# 14.net
KiCad netlist of a schematic drawn in EasyEDA Pro
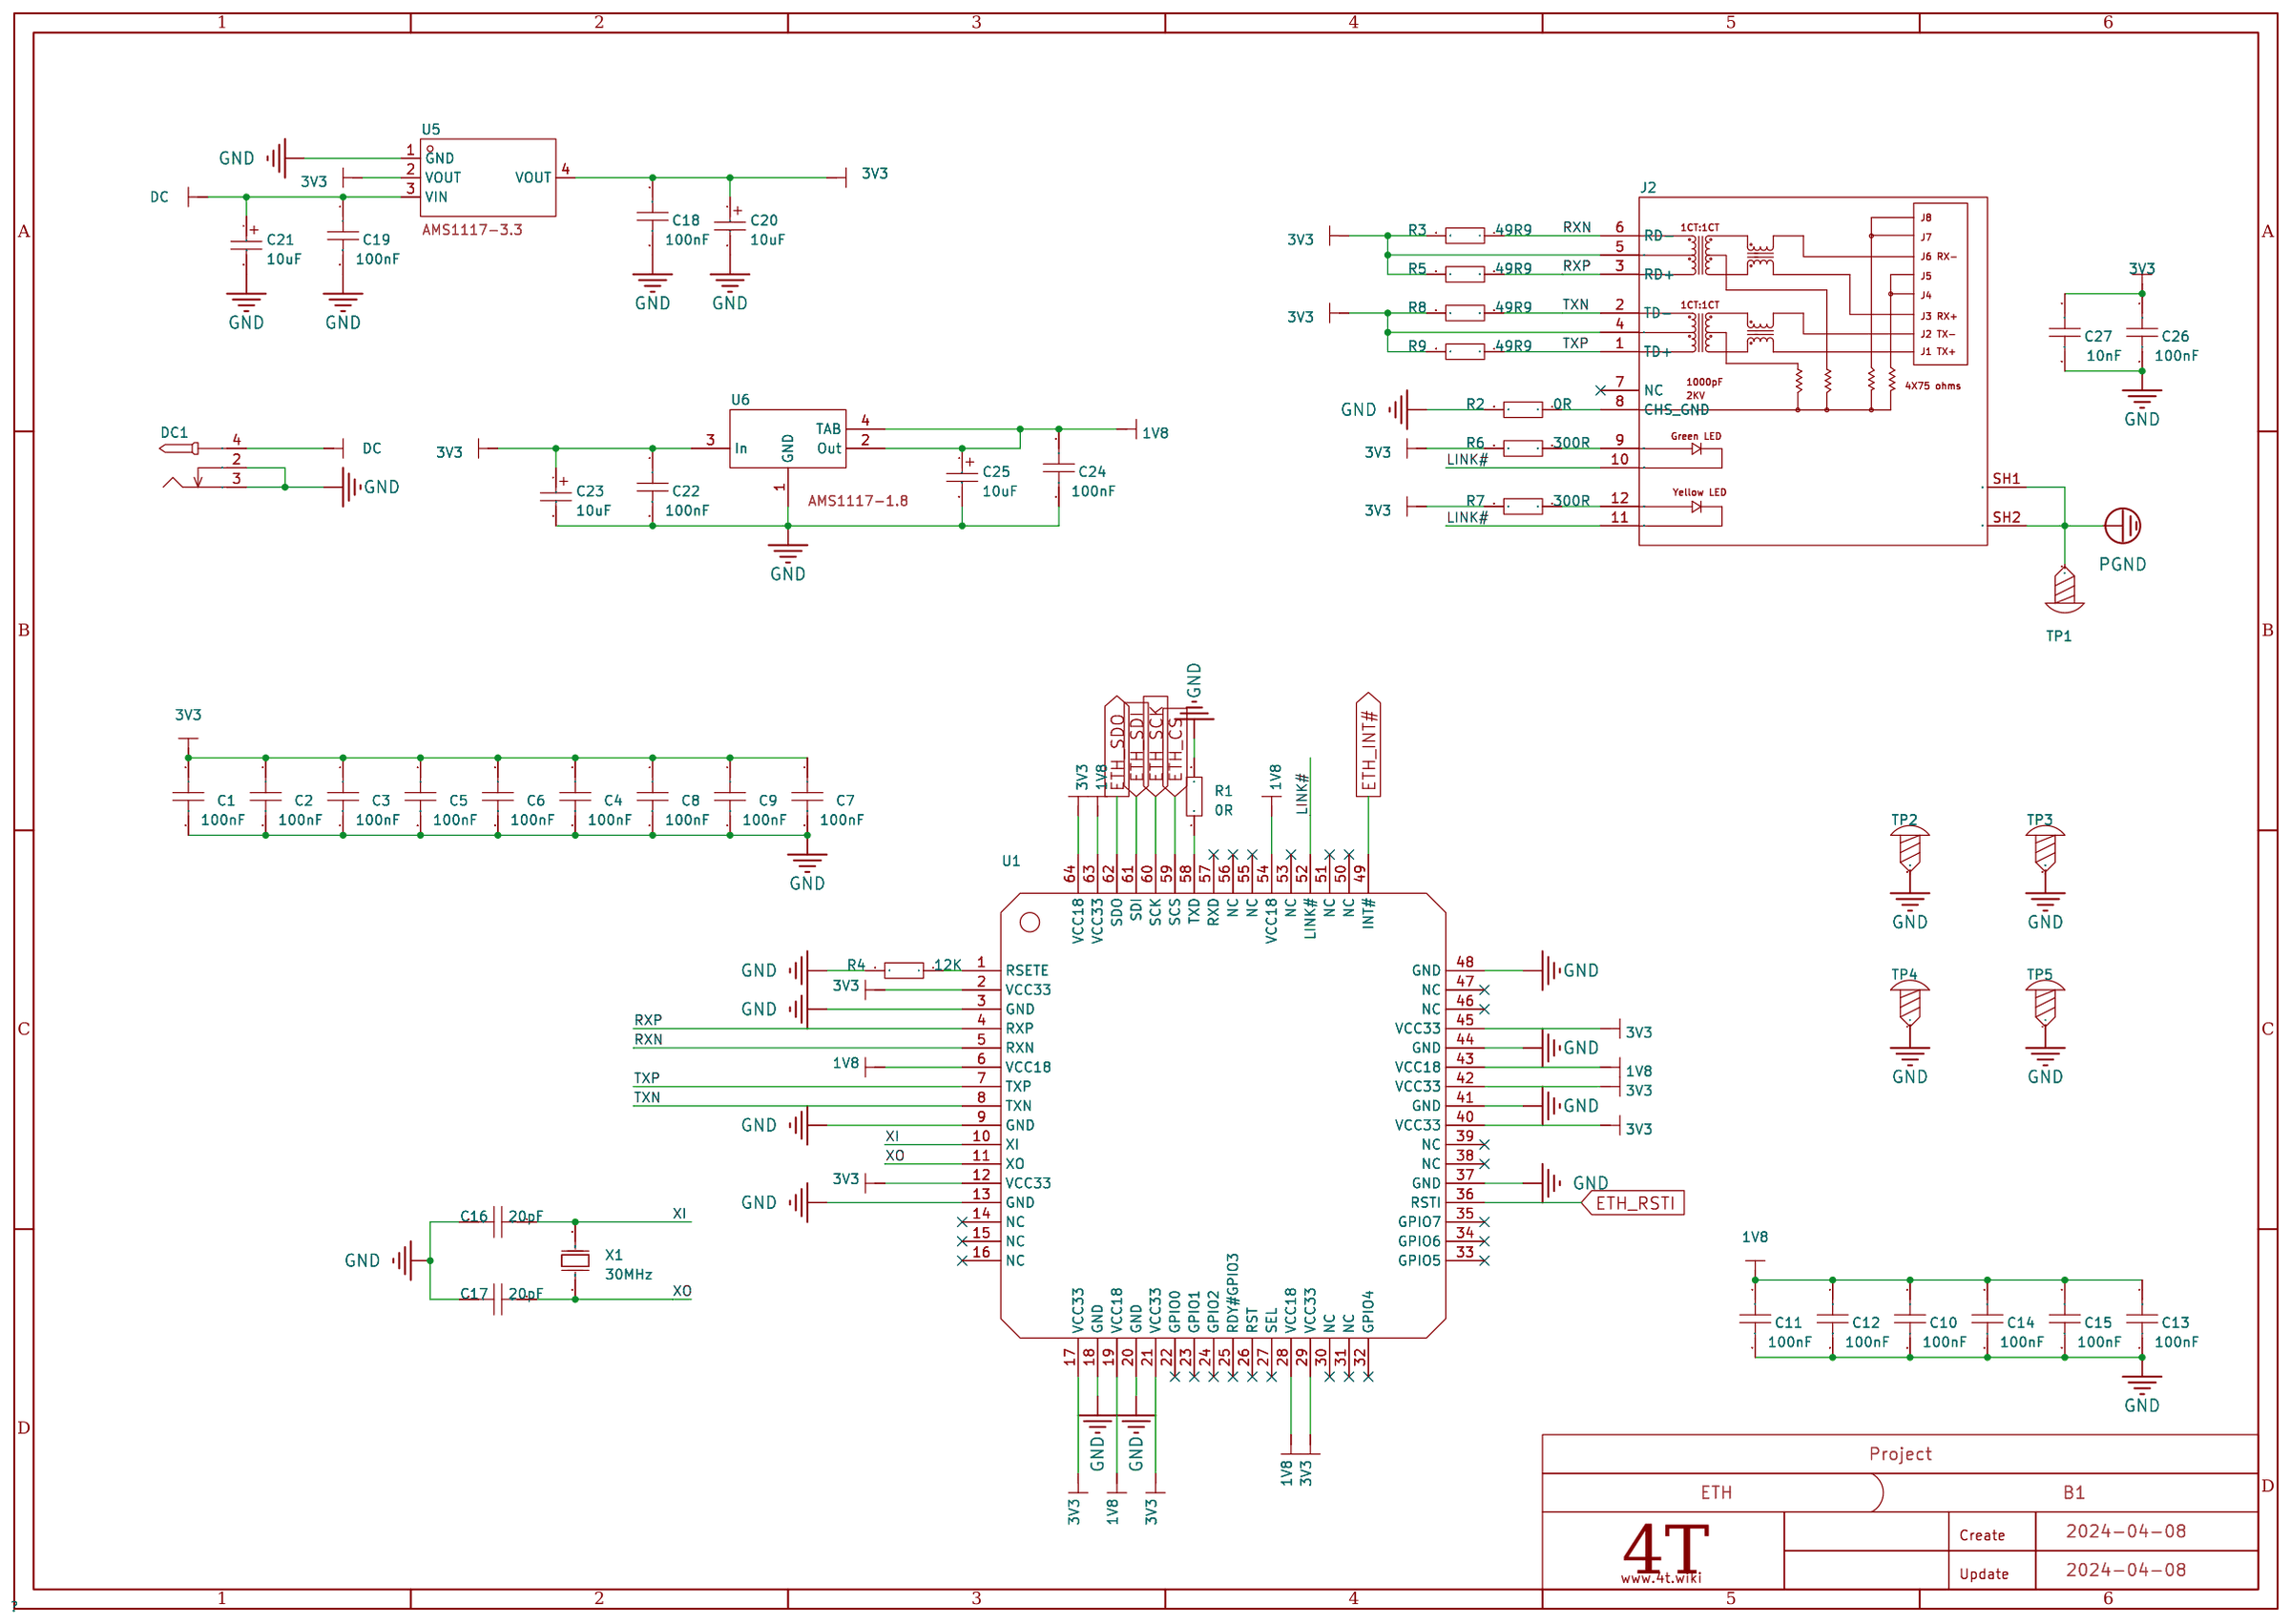
[diagram p0: ETH]
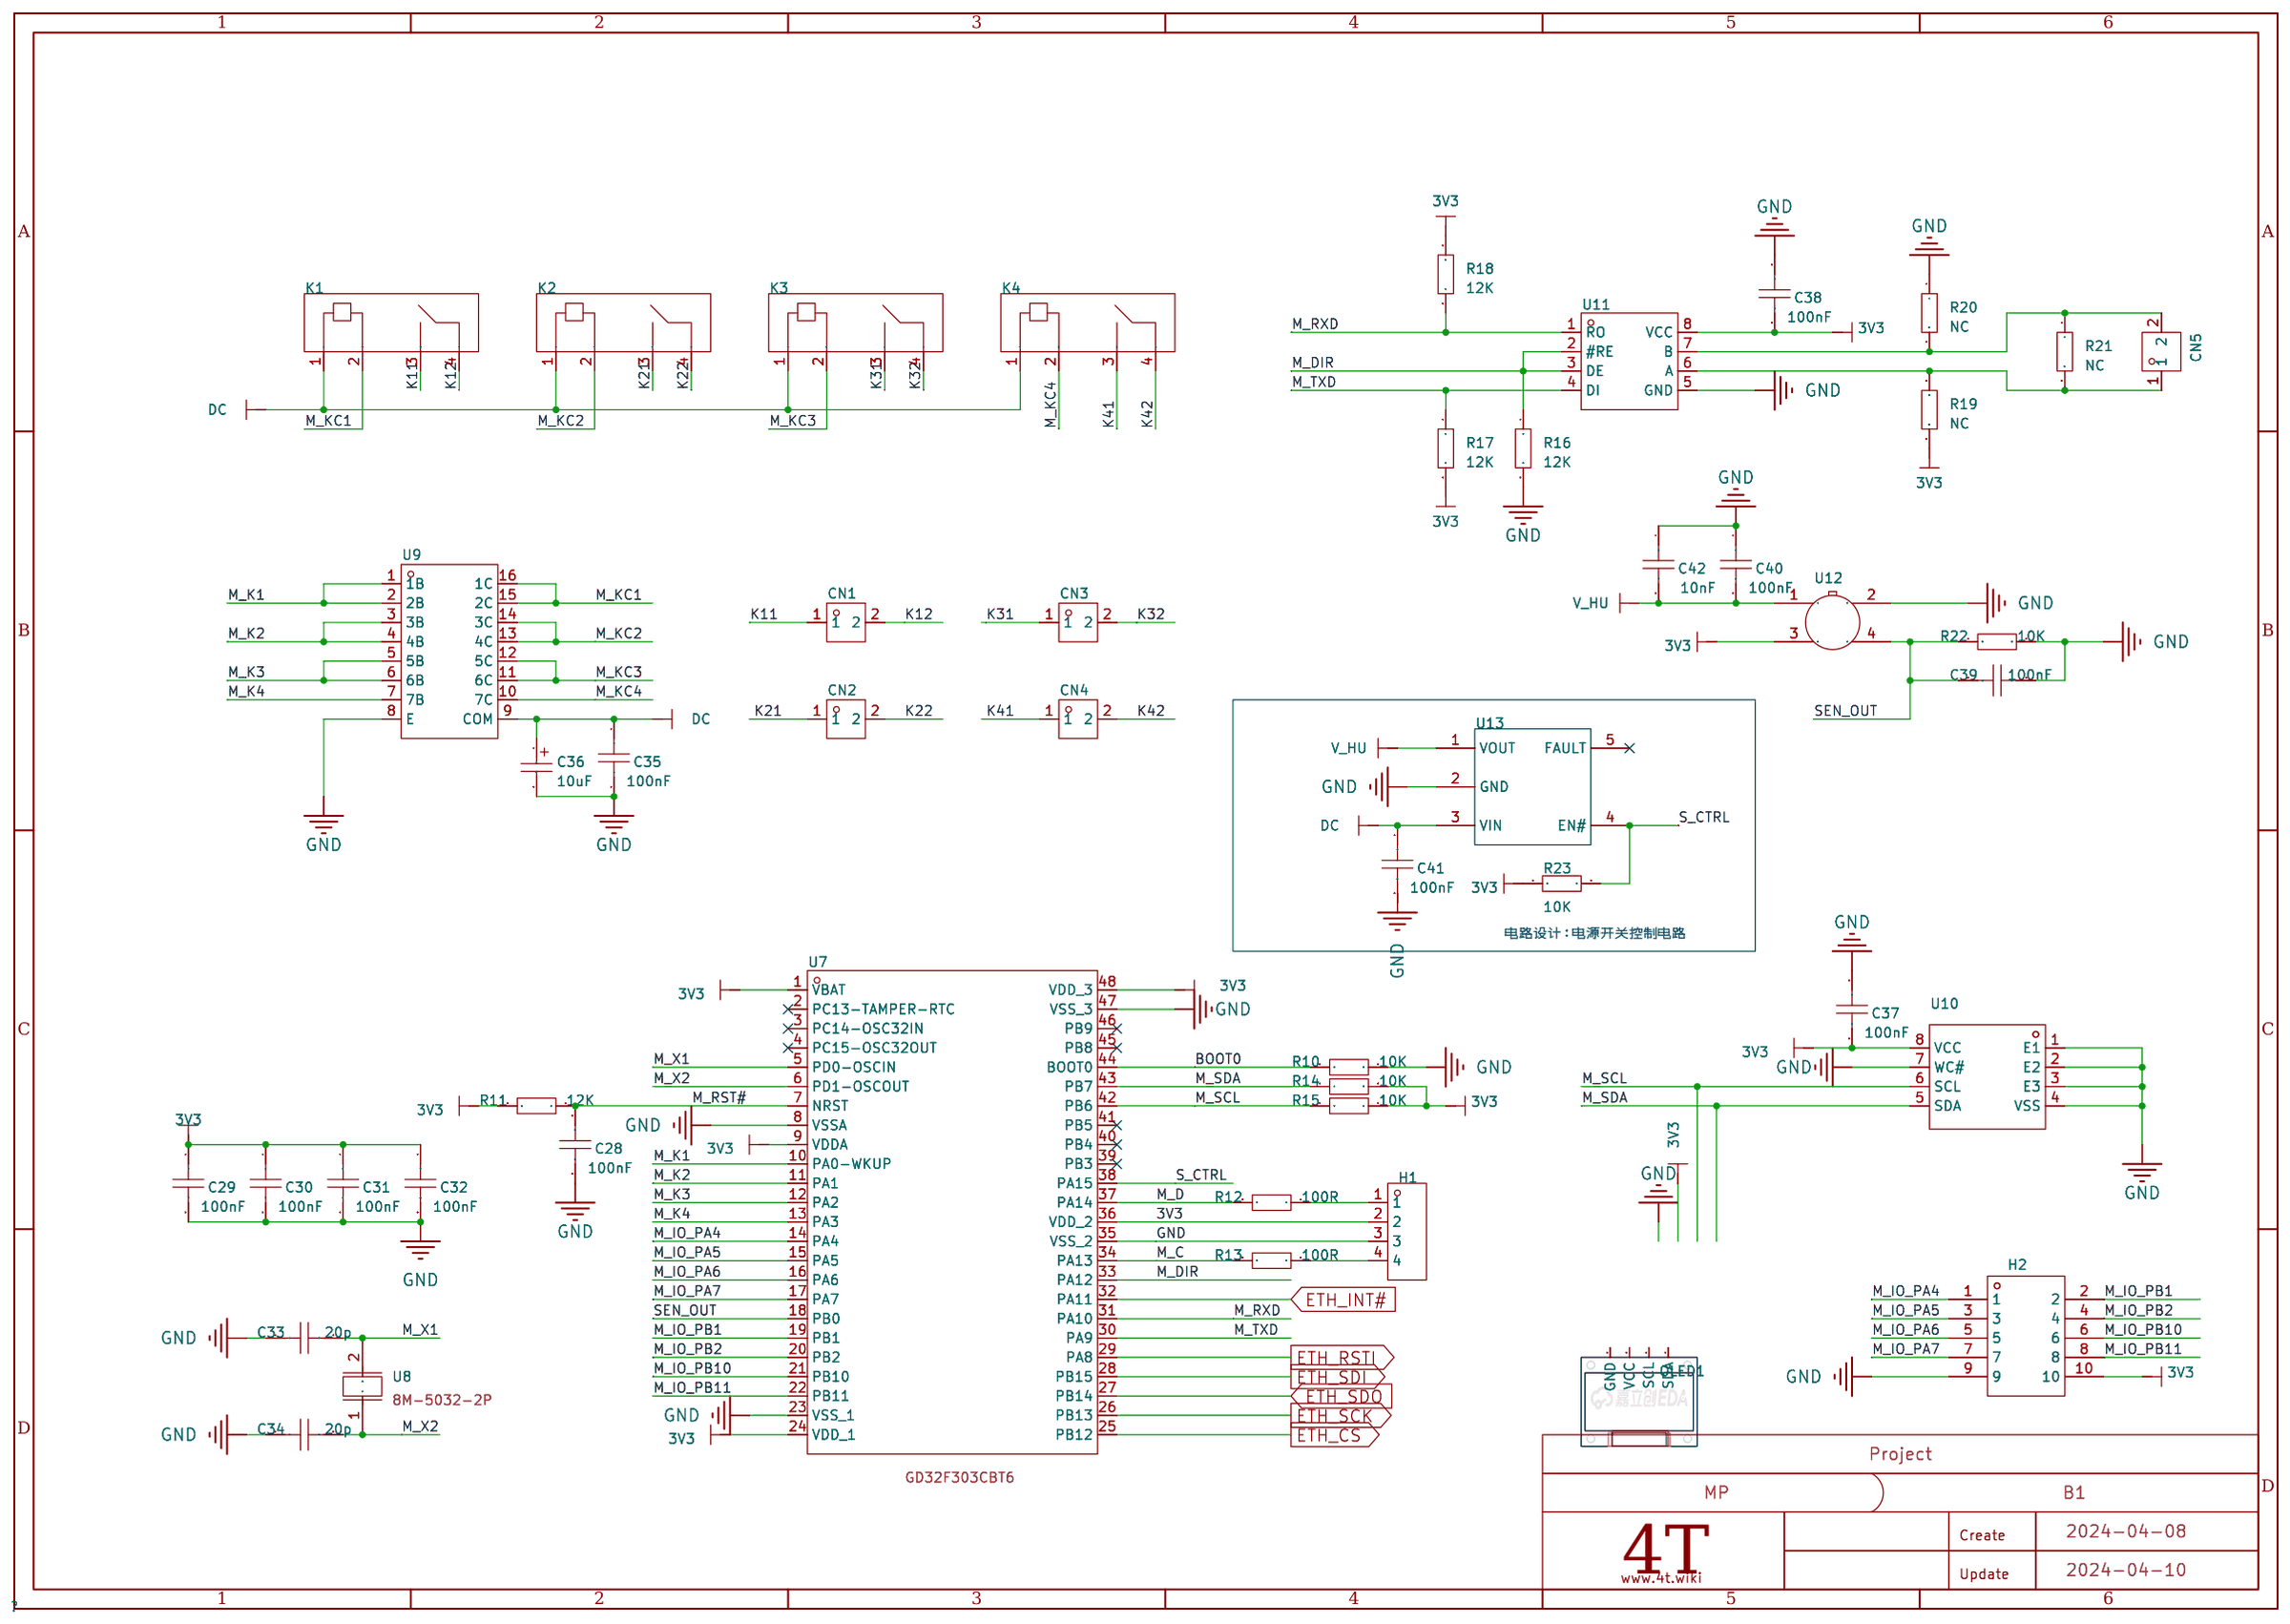
[diagram p1: MP]

(export (version "E")
  (design (tool "Eeschema 10.0.6"))
  (components
    (comp (ref "C1")
      (value "100nF")
      (footprint "easyedapro:C0805")
      (libsource (lib "easyedapro") (part "CapAcitance"))
    )
    (comp (ref "C2")
      (value "100nF")
      (footprint "easyedapro:C0805")
      (libsource (lib "easyedapro") (part "CapAcitance"))
    )
    (comp (ref "C3")
      (value "100nF")
      (footprint "easyedapro:C0805")
      (libsource (lib "easyedapro") (part "CapAcitance"))
    )
    (comp (ref "C4")
      (value "100nF")
      (footprint "easyedapro:C0805")
      (libsource (lib "easyedapro") (part "CapAcitance"))
    )
    (comp (ref "C5")
      (value "100nF")
      (footprint "easyedapro:C0805")
      (libsource (lib "easyedapro") (part "CapAcitance"))
    )
    (comp (ref "C6")
      (value "100nF")
      (footprint "easyedapro:C0805")
      (libsource (lib "easyedapro") (part "CapAcitance"))
    )
    (comp (ref "C7")
      (value "100nF")
      (footprint "easyedapro:C0805")
      (libsource (lib "easyedapro") (part "CapAcitance"))
    )
    (comp (ref "C8")
      (value "100nF")
      (footprint "easyedapro:C0805")
      (libsource (lib "easyedapro") (part "CapAcitance"))
    )
    (comp (ref "C9")
      (value "100nF")
      (footprint "easyedapro:C0805")
      (libsource (lib "easyedapro") (part "CapAcitance"))
    )
    (comp (ref "C10")
      (value "100nF")
      (footprint "easyedapro:C0805")
      (libsource (lib "easyedapro") (part "CapAcitance"))
    )
    (comp (ref "C11")
      (value "100nF")
      (footprint "easyedapro:C0805")
      (libsource (lib "easyedapro") (part "CapAcitance"))
    )
    (comp (ref "C12")
      (value "100nF")
      (footprint "easyedapro:C0805")
      (libsource (lib "easyedapro") (part "CapAcitance"))
    )
    (comp (ref "C13")
      (value "100nF")
      (footprint "easyedapro:C0805")
      (libsource (lib "easyedapro") (part "CapAcitance"))
    )
    (comp (ref "C14")
      (value "100nF")
      (footprint "easyedapro:C0805")
      (libsource (lib "easyedapro") (part "CapAcitance"))
    )
    (comp (ref "C15")
      (value "100nF")
      (footprint "easyedapro:C0805")
      (libsource (lib "easyedapro") (part "CapAcitance"))
    )
    (comp (ref "C16")
      (value "20pF")
      (footprint "easyedapro:C0805")
      (libsource (lib "easyedapro") (part "CapAcitance"))
    )
    (comp (ref "C17")
      (value "20pF")
      (footprint "easyedapro:C0805")
      (libsource (lib "easyedapro") (part "CapAcitance"))
    )
    (comp (ref "C18")
      (value "100nF")
      (footprint "easyedapro:C0805")
      (libsource (lib "easyedapro") (part "CapAcitance"))
    )
    (comp (ref "C19")
      (value "100nF")
      (footprint "easyedapro:C0805")
      (libsource (lib "easyedapro") (part "CapAcitance"))
    )
    (comp (ref "C20")
      (value "10uF")
      (footprint "easyedapro:C_Ele_SMD_3x5.4mm")
      (libsource (lib "easyedapro") (part "CAP"))
    )
    (comp (ref "C21")
      (value "10uF")
      (footprint "easyedapro:C_Ele_SMD_3x5.4mm")
      (libsource (lib "easyedapro") (part "CAP"))
    )
    (comp (ref "C22")
      (value "100nF")
      (footprint "easyedapro:C0805")
      (libsource (lib "easyedapro") (part "CapAcitance"))
    )
    (comp (ref "C23")
      (value "10uF")
      (footprint "easyedapro:C_Ele_SMD_3x5.4mm")
      (libsource (lib "easyedapro") (part "CAP"))
    )
    (comp (ref "C24")
      (value "100nF")
      (footprint "easyedapro:C0805")
      (libsource (lib "easyedapro") (part "CapAcitance"))
    )
    (comp (ref "C25")
      (value "10uF")
      (footprint "easyedapro:C_Ele_SMD_3x5.4mm")
      (libsource (lib "easyedapro") (part "CAP"))
    )
    (comp (ref "C26")
      (value "100nF")
      (footprint "easyedapro:C0805")
      (libsource (lib "easyedapro") (part "CapAcitance"))
    )
    (comp (ref "C27")
      (value "10nF")
      (footprint "easyedapro:C0805")
      (libsource (lib "easyedapro") (part "CapAcitance"))
    )
    (comp (ref "DC1")
      (value "~")
      (footprint "easyedapro:DC-2.0")
      (libsource (lib "easyedapro") (part "DC电源接口"))
    )
    (comp (ref "J2")
      (value "HY911105AE")
      (footprint "easyedapro:RJ45-TH_HR911105A")
      (description "连接器类型:RJ插座;USOC代码:RJ45;端口数量:1;等级:-;屏蔽:-;LED:-;")
      (fields (field (name "Manufacturer") "HANRUN(汉仁)"))
      (libsource (lib "easyedapro") (part "HY911105AE"))
    )
    (comp (ref "R1") (value "0R") (footprint "easyedapro:R0805") (libsource (lib "easyedapro") (part "电阻")))
    (comp (ref "R2") (value "0R") (footprint "easyedapro:R0805") (libsource (lib "easyedapro") (part "电阻")))
    (comp (ref "R3") (value "49R9") (footprint "easyedapro:R0805") (libsource (lib "easyedapro") (part "电阻")))
    (comp (ref "R4") (value "12K") (footprint "easyedapro:R0805") (libsource (lib "easyedapro") (part "电阻")))
    (comp (ref "R5") (value "49R9") (footprint "easyedapro:R0805") (libsource (lib "easyedapro") (part "电阻")))
    (comp (ref "R6") (value "300R") (footprint "easyedapro:R0805") (libsource (lib "easyedapro") (part "电阻")))
    (comp (ref "R7") (value "300R") (footprint "easyedapro:R0805") (libsource (lib "easyedapro") (part "电阻")))
    (comp (ref "R8") (value "49R9") (footprint "easyedapro:R0805") (libsource (lib "easyedapro") (part "电阻")))
    (comp (ref "R9") (value "49R9") (footprint "easyedapro:R0805") (libsource (lib "easyedapro") (part "电阻")))
    (comp (ref "TP1") (value "~") (footprint "easyedapro:M2螺丝") (libsource (lib "easyedapro") (part "螺丝孔")))
    (comp (ref "TP2") (value "~") (footprint "easyedapro:M2螺丝") (libsource (lib "easyedapro") (part "螺丝孔")))
    (comp (ref "TP3") (value "~") (footprint "easyedapro:M2螺丝") (libsource (lib "easyedapro") (part "螺丝孔")))
    (comp (ref "TP4") (value "~") (footprint "easyedapro:M2螺丝") (libsource (lib "easyedapro") (part "螺丝孔")))
    (comp (ref "TP5") (value "~") (footprint "easyedapro:M2螺丝") (libsource (lib "easyedapro") (part "螺丝孔")))
    (comp (ref "U1")
      (value "CH395Q")
      (footprint "easyedapro:LQFP-64_L10.0-W10.0-P0.50-LS12.0-BL")
      (description "应用功能:以太网控制器;通道数:-;接口类型:Parallel, SPI, UART;电源电压:1.65V~3.6V;电源电流:90mA;")
      (fields (field (name "Manufacturer") "WCH(南京沁恒)"))
      (libsource (lib "easyedapro") (part "CH395Q"))
    )
    (comp (ref "U5")
      (value "AMS1117-3.3")
      (footprint "easyedapro:SOT-223-3_L6.5-W3.4-P2.30-LS7.0-BR")
      (fields (field (name "Manufacturer Part") "AMS1117-3.3") (field (name "Manufacturer") "AMS"))
      (libsource (lib "easyedapro") (part "AMS1117-3.3"))
    )
    (comp (ref "U6")
      (value "AMS1117-1.8")
      (footprint "easyedapro:SOT-223-4_L6.5-W3.5-P2.30-LS7.0-BR")
      (description "输出类型:固定;输出极性:正;输出通道数:1;最大输入电压:15V;输出电压:1.8V~1.8V;压差:1.3V@(1A);输出电流:1A;电源纹波抑制比(PSRR):75dB@(120Hz);")
      (fields (field (name "Manufacturer Part") "AMS1117-1.8") (field (name "Manufacturer") "AMS"))
      (libsource (lib "easyedapro") (part "AMS1117-1.8"))
    )
    (comp (ref "X1")
      (value "30MHz")
      (footprint "easyedapro:OSC-SMD_L5.0-W3.2")
      (description "晶振类型:贴片无源晶振;频率:30MHz;频率公差:±10ppm;频率稳定度:±50ppm;负载电容:20pF;工作温度:-40℃~+85℃;")
      (fields (field (name "Manufacturer Part") "X503230MSB2GI") (field (name "Manufacturer") "YXC(扬兴晶振)"))
      (libsource (lib "easyedapro") (part "X503230MSB2GI"))
    )
    (comp (ref "C28")
      (value "100nF")
      (footprint "easyedapro:C0805")
      (libsource (lib "easyedapro") (part "CapAcitance"))
    )
    (comp (ref "C29")
      (value "100nF")
      (footprint "easyedapro:C0805")
      (libsource (lib "easyedapro") (part "CapAcitance"))
    )
    (comp (ref "C30")
      (value "100nF")
      (footprint "easyedapro:C0805")
      (libsource (lib "easyedapro") (part "CapAcitance"))
    )
    (comp (ref "C31")
      (value "100nF")
      (footprint "easyedapro:C0805")
      (libsource (lib "easyedapro") (part "CapAcitance"))
    )
    (comp (ref "C32")
      (value "100nF")
      (footprint "easyedapro:C0805")
      (libsource (lib "easyedapro") (part "CapAcitance"))
    )
    (comp (ref "C33")
      (value "20p")
      (footprint "easyedapro:C0805")
      (libsource (lib "easyedapro") (part "CapAcitance"))
    )
    (comp (ref "C34")
      (value "20p")
      (footprint "easyedapro:C0805")
      (libsource (lib "easyedapro") (part "CapAcitance"))
    )
    (comp (ref "C35")
      (value "100nF")
      (footprint "easyedapro:C0805")
      (libsource (lib "easyedapro") (part "CapAcitance"))
    )
    (comp (ref "C36")
      (value "10uF")
      (footprint "easyedapro:C_Ele_SMD_3x5.4mm")
      (libsource (lib "easyedapro") (part "CAP"))
    )
    (comp (ref "C37")
      (value "100nF")
      (footprint "easyedapro:C0805")
      (libsource (lib "easyedapro") (part "CapAcitance"))
    )
    (comp (ref "C38")
      (value "100nF")
      (footprint "easyedapro:C0805")
      (libsource (lib "easyedapro") (part "CapAcitance"))
    )
    (comp (ref "C39")
      (value "100nF")
      (footprint "easyedapro:C0805")
      (libsource (lib "easyedapro") (part "CapAcitance"))
    )
    (comp (ref "C40")
      (value "100nF")
      (footprint "easyedapro:C0805")
      (libsource (lib "easyedapro") (part "CapAcitance"))
    )
    (comp (ref "C41")
      (value "100nF")
      (footprint "easyedapro:C0805")
      (libsource (lib "easyedapro") (part "CapAcitance"))
    )
    (comp (ref "C42")
      (value "10nF")
      (footprint "easyedapro:C0805")
      (libsource (lib "easyedapro") (part "CapAcitance"))
    )
    (comp (ref "CN1")
      (value "KF128L-5.08-2P 蓝色")
      (footprint "easyedapro:TH_KF128L-5.08-2P")
      (libsource (lib "easyedapro") (part "KF128L-5.08-2P 蓝色"))
    )
    (comp (ref "CN2")
      (value "KF128L-5.08-2P 蓝色")
      (footprint "easyedapro:TH_KF128L-5.08-2P")
      (libsource (lib "easyedapro") (part "KF128L-5.08-2P 蓝色"))
    )
    (comp (ref "CN3")
      (value "KF128L-5.08-2P 蓝色")
      (footprint "easyedapro:TH_KF128L-5.08-2P")
      (libsource (lib "easyedapro") (part "KF128L-5.08-2P 蓝色"))
    )
    (comp (ref "CN4")
      (value "KF128L-5.08-2P 蓝色")
      (footprint "easyedapro:TH_KF128L-5.08-2P")
      (libsource (lib "easyedapro") (part "KF128L-5.08-2P 蓝色"))
    )
    (comp (ref "CN5")
      (value "KF128L-5.08-2P 蓝色")
      (footprint "easyedapro:TH_KF128L-5.08-2P")
      (libsource (lib "easyedapro") (part "KF128L-5.08-2P 蓝色"))
    )
    (comp (ref "H1")
      (value "~")
      (footprint "easyedapro:HDR-TH_4P-P2.54-V-F")
      (libsource (lib "easyedapro") (part "2.54-1*4P母"))
    )
    (comp (ref "H2")
      (value "~")
      (footprint "easyedapro:HDR-TH_10P-P2.54-V-M-R2-C5-S2.54")
      (libsource (lib "easyedapro") (part "HDR-M-2.54_2x5"))
    )
    (comp (ref "K1")
      (value "HF49FD/012-1H12")
      (footprint "easyedapro:RELAY-TH_HF49FD-XXX-1H12-XXX")
      (description "线圈电压:12V;线圈类型:非极化-单线圈;触点形式:一组常开:1A(单刀单掷-常开);最大切换电流:5A;触点材料:AgNi;")
      (fields (field (name "Manufacturer") "HF(宏发)"))
      (libsource (lib "easyedapro") (part "HF49FD/012-1H12"))
    )
    (comp (ref "K2")
      (value "HF49FD/012-1H12")
      (footprint "easyedapro:RELAY-TH_HF49FD-XXX-1H12-XXX")
      (description "线圈电压:12V;线圈类型:非极化-单线圈;触点形式:一组常开:1A(单刀单掷-常开);最大切换电流:5A;触点材料:AgNi;")
      (fields (field (name "Manufacturer") "HF(宏发)"))
      (libsource (lib "easyedapro") (part "HF49FD/012-1H12"))
    )
    (comp (ref "K3")
      (value "HF49FD/012-1H12")
      (footprint "easyedapro:RELAY-TH_HF49FD-XXX-1H12-XXX")
      (description "线圈电压:12V;线圈类型:非极化-单线圈;触点形式:一组常开:1A(单刀单掷-常开);最大切换电流:5A;触点材料:AgNi;")
      (fields (field (name "Manufacturer") "HF(宏发)"))
      (libsource (lib "easyedapro") (part "HF49FD/012-1H12"))
    )
    (comp (ref "K4")
      (value "HF49FD/012-1H12")
      (footprint "easyedapro:RELAY-TH_HF49FD-XXX-1H12-XXX")
      (description "线圈电压:12V;线圈类型:非极化-单线圈;触点形式:一组常开:1A(单刀单掷-常开);最大切换电流:5A;触点材料:AgNi;")
      (fields (field (name "Manufacturer") "HF(宏发)"))
      (libsource (lib "easyedapro") (part "HF49FD/012-1H12"))
    )
    (comp (ref "OLED1")
      (value "~")
      (footprint "easyedapro:0.96OLED_4P")
      (libsource (lib "easyedapro") (part "0.96OLED模块_4P"))
    )
    (comp (ref "R10") (value "10K") (footprint "easyedapro:R0805") (libsource (lib "easyedapro") (part "电阻")))
    (comp (ref "R11") (value "12K") (footprint "easyedapro:R0805") (libsource (lib "easyedapro") (part "电阻")))
    (comp (ref "R12")
      (value "100R")
      (footprint "easyedapro:R0805")
      (libsource (lib "easyedapro") (part "电阻"))
    )
    (comp (ref "R13")
      (value "100R")
      (footprint "easyedapro:R0805")
      (libsource (lib "easyedapro") (part "电阻"))
    )
    (comp (ref "R14") (value "10K") (footprint "easyedapro:R0805") (libsource (lib "easyedapro") (part "电阻")))
    (comp (ref "R15") (value "10K") (footprint "easyedapro:R0805") (libsource (lib "easyedapro") (part "电阻")))
    (comp (ref "R16") (value "12K") (footprint "easyedapro:R0805") (libsource (lib "easyedapro") (part "电阻")))
    (comp (ref "R17") (value "12K") (footprint "easyedapro:R0805") (libsource (lib "easyedapro") (part "电阻")))
    (comp (ref "R18") (value "12K") (footprint "easyedapro:R0805") (libsource (lib "easyedapro") (part "电阻")))
    (comp (ref "R19") (value "NC") (footprint "easyedapro:R0805") (libsource (lib "easyedapro") (part "电阻")))
    (comp (ref "R20") (value "NC") (footprint "easyedapro:R0805") (libsource (lib "easyedapro") (part "电阻")))
    (comp (ref "R21") (value "NC") (footprint "easyedapro:R0805") (libsource (lib "easyedapro") (part "电阻")))
    (comp (ref "R22") (value "10K") (footprint "easyedapro:R0805") (libsource (lib "easyedapro") (part "电阻")))
    (comp (ref "R23") (value "10K") (footprint "easyedapro:R0805") (libsource (lib "easyedapro") (part "电阻")))
    (comp (ref "U7")
      (value "GD32F303CBT6")
      (footprint "easyedapro:LQFP-48_L7.0-W7.0-P0.50-LS9.0-BL")
      (fields
        (field (name "Manufacturer Part") "GD32F303CBT6")
        (field (name "Manufacturer") "GigaDevice(兆易创新)")
      )
      (libsource (lib "easyedapro") (part "GD32F303CBT6"))
    )
    (comp (ref "U8")
      (value "8M-5032-2P")
      (footprint "easyedapro:CRYSTAL-SMD_L5.0-W3.2")
      (fields (field (name "Manufacturer Part") "8M-5032-2P"))
      (libsource (lib "easyedapro") (part "8M-5032-2P"))
    )
    (comp (ref "U9")
      (value "ULN2003")
      (footprint "easyedapro:SOIC-16_L9.9-W3.9-P1.27-LS6.0-BL")
      (fields (field (name "Manufacturer") "IDCHIP(英锐芯)"))
      (libsource (lib "easyedapro") (part "ULN2003_C688859"))
    )
    (comp (ref "U10")
      (value "M24C02-WMN6TP")
      (footprint "easyedapro:SOIC-8_L4.9-W3.9-P1.27-LS6.0-BL")
      (description "2-Kbit(256 x 8bit)，I2C接口，工作电压：2.5V to 5.5V")
      (fields (field (name "Manufacturer") "ST(意法半导体)"))
      (libsource (lib "easyedapro") (part "M24C02-WMN6TP"))
    )
    (comp (ref "U11")
      (value "MAX3485ESA")
      (footprint "easyedapro:SOP-8_L5.0-W4.0-P1.27-LS6.0-BL")
      (fields (field (name "Manufacturer") "UMW(广东友台半导体)"))
      (libsource (lib "easyedapro") (part "MAX3485ESA"))
    )
    (comp (ref "U12")
      (value "MP-2")
      (footprint "easyedapro:SENSOR-TH_MP-5")
      (fields (field (name "Manufacturer") "Winsen(炜盛)"))
      (libsource (lib "easyedapro") (part "MP-2"))
    )
    (comp (ref "U13")
      (value "~")
      (footprint "easyedapro:SOT_PDS")
      (libsource (lib "easyedapro") (part "PDS"))
    )
  )
  (nets
    (net (code "1") (name "1V8") (class "Default")
      (node (ref "C10") (pin "1") (pinfunction "1_1") (pintype "input"))
      (node (ref "C11") (pin "1") (pinfunction "1_1") (pintype "input"))
      (node (ref "C12") (pin "1") (pinfunction "1_1") (pintype "input"))
      (node (ref "C13") (pin "1") (pinfunction "1_1") (pintype "input"))
      (node (ref "C14") (pin "1") (pinfunction "1_1") (pintype "input"))
      (node (ref "C15") (pin "1") (pinfunction "1_1") (pintype "input"))
      (node (ref "C24") (pin "1") (pinfunction "1_1") (pintype "input"))
      (node (ref "C25") (pin "1") (pinfunction "1_1") (pintype "input"))
      (node (ref "U1") (pin "19") (pinfunction "VCC18_19") (pintype "input"))
      (node (ref "U1") (pin "28") (pinfunction "VCC18_28") (pintype "input"))
      (node (ref "U1") (pin "43") (pinfunction "VCC18_43") (pintype "input"))
      (node (ref "U1") (pin "54") (pinfunction "VCC18_54") (pintype "input"))
      (node (ref "U1") (pin "6") (pinfunction "VCC18_6") (pintype "input"))
      (node (ref "U1") (pin "63") (pinfunction "VCC33_63") (pintype "input"))
      (node (ref "U6") (pin "2") (pinfunction "Out_2") (pintype "input"))
      (node (ref "U6") (pin "4") (pinfunction "TAB_4") (pintype "input"))
    )
    (net (code "2") (name "3V3") (class "Default")
      (node (ref "C1") (pin "1") (pinfunction "1_1") (pintype "input"))
      (node (ref "C18") (pin "1") (pinfunction "1_1") (pintype "input"))
      (node (ref "C2") (pin "1") (pinfunction "1_1") (pintype "input"))
      (node (ref "C20") (pin "1") (pinfunction "1_1") (pintype "input"))
      (node (ref "C22") (pin "1") (pinfunction "1_1") (pintype "input"))
      (node (ref "C23") (pin "1") (pinfunction "1_1") (pintype "input"))
      (node (ref "C26") (pin "1") (pinfunction "1_1") (pintype "input"))
      (node (ref "C27") (pin "1") (pinfunction "1_1") (pintype "input"))
      (node (ref "C29") (pin "1") (pinfunction "1_1") (pintype "input"))
      (node (ref "C3") (pin "1") (pinfunction "1_1") (pintype "input"))
      (node (ref "C30") (pin "1") (pinfunction "1_1") (pintype "input"))
      (node (ref "C31") (pin "1") (pinfunction "1_1") (pintype "input"))
      (node (ref "C32") (pin "1") (pinfunction "1_1") (pintype "input"))
      (node (ref "C37") (pin "2") (pinfunction "2_2") (pintype "input"))
      (node (ref "C38") (pin "2") (pinfunction "2_2") (pintype "input"))
      (node (ref "C4") (pin "1") (pinfunction "1_1") (pintype "input"))
      (node (ref "C5") (pin "1") (pinfunction "1_1") (pintype "input"))
      (node (ref "C6") (pin "1") (pinfunction "1_1") (pintype "input"))
      (node (ref "C7") (pin "1") (pinfunction "1_1") (pintype "input"))
      (node (ref "C8") (pin "1") (pinfunction "1_1") (pintype "input"))
      (node (ref "C9") (pin "1") (pinfunction "1_1") (pintype "input"))
      (node (ref "H1") (pin "2") (pinfunction "2_2") (pintype "input"))
      (node (ref "H2") (pin "10") (pinfunction "10_10") (pintype "input"))
      (node (ref "J2") (pin "4") (pinfunction "4_4") (pintype "input"))
      (node (ref "J2") (pin "5") (pinfunction "5_5") (pintype "input"))
      (node (ref "R11") (pin "2") (pinfunction "2_2") (pintype "input"))
      (node (ref "R14") (pin "2") (pinfunction "2_2") (pintype "input"))
      (node (ref "R15") (pin "1") (pinfunction "1_1") (pintype "input"))
      (node (ref "R17") (pin "2") (pinfunction "2_2") (pintype "input"))
      (node (ref "R18") (pin "1") (pinfunction "1_1") (pintype "input"))
      (node (ref "R19") (pin "2") (pinfunction "2_2") (pintype "input"))
      (node (ref "R23") (pin "1") (pinfunction "1_1") (pintype "input"))
      (node (ref "R3") (pin "2") (pinfunction "2_2") (pintype "input"))
      (node (ref "R5") (pin "2") (pinfunction "2_2") (pintype "input"))
      (node (ref "R6") (pin "2") (pinfunction "2_2") (pintype "input"))
      (node (ref "R7") (pin "2") (pinfunction "2_2") (pintype "input"))
      (node (ref "R8") (pin "2") (pinfunction "2_2") (pintype "input"))
      (node (ref "R9") (pin "2") (pinfunction "2_2") (pintype "input"))
      (node (ref "U1") (pin "12") (pinfunction "VCC33_12") (pintype "input"))
      (node (ref "U1") (pin "17") (pinfunction "VCC33_17") (pintype "input"))
      (node (ref "U1") (pin "2") (pinfunction "VCC33_2") (pintype "input"))
      (node (ref "U1") (pin "21") (pinfunction "VCC33_21") (pintype "input"))
      (node (ref "U1") (pin "29") (pinfunction "VCC33_29") (pintype "input"))
      (node (ref "U1") (pin "40") (pinfunction "VCC33_40") (pintype "input"))
      (node (ref "U1") (pin "42") (pinfunction "VCC33_42") (pintype "input"))
      (node (ref "U1") (pin "45") (pinfunction "VCC33_45") (pintype "input"))
      (node (ref "U1") (pin "64") (pinfunction "VCC18_64") (pintype "input"))
      (node (ref "U10") (pin "8") (pinfunction "VCC_8") (pintype "input"))
      (node (ref "U11") (pin "8") (pinfunction "VCC_8") (pintype "input"))
      (node (ref "U12") (pin "3") (pinfunction "3_3") (pintype "input"))
      (node (ref "U5") (pin "2") (pinfunction "VOUT_2") (pintype "input"))
      (node (ref "U5") (pin "4") (pinfunction "VOUT_4") (pintype "input"))
      (node (ref "U6") (pin "3") (pinfunction "In_3") (pintype "input"))
      (node (ref "U7") (pin "1") (pinfunction "VBAT_1") (pintype "input"))
      (node (ref "U7") (pin "24") (pinfunction "VDD_1_24") (pintype "input"))
      (node (ref "U7") (pin "36") (pinfunction "VDD_2_36") (pintype "input"))
      (node (ref "U7") (pin "48") (pinfunction "VDD_3_48") (pintype "input"))
      (node (ref "U7") (pin "9") (pinfunction "VDDA_9") (pintype "input"))
    )
    (net (code "3") (name "BOOT0") (class "Default")
      (node (ref "R10") (pin "2") (pinfunction "2_2") (pintype "input"))
      (node (ref "U7") (pin "44") (pinfunction "BOOT0_44") (pintype "input"))
    )
    (net (code "4") (name "DC") (class "Default")
      (node (ref "C19") (pin "1") (pinfunction "1_1") (pintype "input"))
      (node (ref "C21") (pin "1") (pinfunction "1_1") (pintype "input"))
      (node (ref "C35") (pin "1") (pinfunction "1_1") (pintype "input"))
      (node (ref "C36") (pin "1") (pinfunction "1_1") (pintype "input"))
      (node (ref "C41") (pin "1") (pinfunction "1_1") (pintype "input"))
      (node (ref "DC1") (pin "4") (pinfunction "4_4") (pintype "input"))
      (node (ref "K1") (pin "1") (pinfunction "1_1") (pintype "input"))
      (node (ref "K2") (pin "1") (pinfunction "1_1") (pintype "input"))
      (node (ref "K3") (pin "1") (pinfunction "1_1") (pintype "input"))
      (node (ref "K4") (pin "1") (pinfunction "1_1") (pintype "input"))
      (node (ref "U13") (pin "3") (pinfunction "VIN_3") (pintype "input"))
      (node (ref "U5") (pin "3") (pinfunction "VIN_3") (pintype "input"))
      (node (ref "U9") (pin "9") (pinfunction "COM_9") (pintype "input"))
    )
    (net (code "5") (name "ETH_CS") (class "Default")
      (node (ref "U1") (pin "59") (pinfunction "SCS_59") (pintype "input"))
      (node (ref "U7") (pin "25") (pinfunction "PB12_25") (pintype "input"))
    )
    (net (code "6") (name "ETH_INT#") (class "Default")
      (node (ref "U1") (pin "49") (pinfunction "INT#_49") (pintype "input"))
      (node (ref "U7") (pin "32") (pinfunction "PA11_32") (pintype "input"))
    )
    (net (code "7") (name "ETH_RSTI") (class "Default")
      (node (ref "U1") (pin "36") (pinfunction "RSTI_36") (pintype "input"))
      (node (ref "U7") (pin "29") (pinfunction "PA8_29") (pintype "input"))
    )
    (net (code "8") (name "ETH_SCK") (class "Default")
      (node (ref "U1") (pin "60") (pinfunction "SCK_60") (pintype "input"))
      (node (ref "U7") (pin "26") (pinfunction "PB13_26") (pintype "input"))
    )
    (net (code "9") (name "ETH_SDI") (class "Default")
      (node (ref "U1") (pin "61") (pinfunction "SDI_61") (pintype "input"))
      (node (ref "U7") (pin "28") (pinfunction "PB15_28") (pintype "input"))
    )
    (net (code "10") (name "ETH_SDO") (class "Default")
      (node (ref "U1") (pin "62") (pinfunction "SDO_62") (pintype "input"))
      (node (ref "U7") (pin "27") (pinfunction "PB14_27") (pintype "input"))
    )
    (net (code "11") (name "GND") (class "Default")
      (node (ref "C1") (pin "2") (pinfunction "2_2") (pintype "input"))
      (node (ref "C10") (pin "2") (pinfunction "2_2") (pintype "input"))
      (node (ref "C11") (pin "2") (pinfunction "2_2") (pintype "input"))
      (node (ref "C12") (pin "2") (pinfunction "2_2") (pintype "input"))
      (node (ref "C13") (pin "2") (pinfunction "2_2") (pintype "input"))
      (node (ref "C14") (pin "2") (pinfunction "2_2") (pintype "input"))
      (node (ref "C15") (pin "2") (pinfunction "2_2") (pintype "input"))
      (node (ref "C16") (pin "1") (pinfunction "1_1") (pintype "input"))
      (node (ref "C17") (pin "1") (pinfunction "1_1") (pintype "input"))
      (node (ref "C18") (pin "2") (pinfunction "2_2") (pintype "input"))
      (node (ref "C19") (pin "2") (pinfunction "2_2") (pintype "input"))
      (node (ref "C2") (pin "2") (pinfunction "2_2") (pintype "input"))
      (node (ref "C20") (pin "2") (pinfunction "2_2") (pintype "input"))
      (node (ref "C21") (pin "2") (pinfunction "2_2") (pintype "input"))
      (node (ref "C22") (pin "2") (pinfunction "2_2") (pintype "input"))
      (node (ref "C23") (pin "2") (pinfunction "2_2") (pintype "input"))
      (node (ref "C24") (pin "2") (pinfunction "2_2") (pintype "input"))
      (node (ref "C25") (pin "2") (pinfunction "2_2") (pintype "input"))
      (node (ref "C26") (pin "2") (pinfunction "2_2") (pintype "input"))
      (node (ref "C27") (pin "2") (pinfunction "2_2") (pintype "input"))
      (node (ref "C28") (pin "2") (pinfunction "2_2") (pintype "input"))
      (node (ref "C29") (pin "2") (pinfunction "2_2") (pintype "input"))
      (node (ref "C3") (pin "2") (pinfunction "2_2") (pintype "input"))
      (node (ref "C30") (pin "2") (pinfunction "2_2") (pintype "input"))
      (node (ref "C31") (pin "2") (pinfunction "2_2") (pintype "input"))
      (node (ref "C32") (pin "2") (pinfunction "2_2") (pintype "input"))
      (node (ref "C33") (pin "1") (pinfunction "1_1") (pintype "input"))
      (node (ref "C34") (pin "1") (pinfunction "1_1") (pintype "input"))
      (node (ref "C35") (pin "2") (pinfunction "2_2") (pintype "input"))
      (node (ref "C36") (pin "2") (pinfunction "2_2") (pintype "input"))
      (node (ref "C37") (pin "1") (pinfunction "1_1") (pintype "input"))
      (node (ref "C38") (pin "1") (pinfunction "1_1") (pintype "input"))
      (node (ref "C39") (pin "2") (pinfunction "2_2") (pintype "input"))
      (node (ref "C4") (pin "2") (pinfunction "2_2") (pintype "input"))
      (node (ref "C40") (pin "1") (pinfunction "1_1") (pintype "input"))
      (node (ref "C41") (pin "2") (pinfunction "2_2") (pintype "input"))
      (node (ref "C42") (pin "1") (pinfunction "1_1") (pintype "input"))
      (node (ref "C5") (pin "2") (pinfunction "2_2") (pintype "input"))
      (node (ref "C6") (pin "2") (pinfunction "2_2") (pintype "input"))
      (node (ref "C7") (pin "2") (pinfunction "2_2") (pintype "input"))
      (node (ref "C8") (pin "2") (pinfunction "2_2") (pintype "input"))
      (node (ref "C9") (pin "2") (pinfunction "2_2") (pintype "input"))
      (node (ref "DC1") (pin "2") (pinfunction "2_2") (pintype "input"))
      (node (ref "DC1") (pin "3") (pinfunction "3_3") (pintype "input"))
      (node (ref "H1") (pin "3") (pinfunction "3_3") (pintype "input"))
      (node (ref "H2") (pin "9") (pinfunction "9_9") (pintype "input"))
      (node (ref "R1") (pin "2") (pinfunction "2_2") (pintype "input"))
      (node (ref "R10") (pin "1") (pinfunction "1_1") (pintype "input"))
      (node (ref "R16") (pin "2") (pinfunction "2_2") (pintype "input"))
      (node (ref "R2") (pin "2") (pinfunction "2_2") (pintype "input"))
      (node (ref "R20") (pin "1") (pinfunction "1_1") (pintype "input"))
      (node (ref "R22") (pin "2") (pinfunction "2_2") (pintype "input"))
      (node (ref "R4") (pin "2") (pinfunction "2_2") (pintype "input"))
      (node (ref "TP2") (pin "1") (pinfunction "1_1") (pintype "input"))
      (node (ref "TP3") (pin "1") (pinfunction "1_1") (pintype "input"))
      (node (ref "TP4") (pin "1") (pinfunction "1_1") (pintype "input"))
      (node (ref "TP5") (pin "1") (pinfunction "1_1") (pintype "input"))
      (node (ref "U1") (pin "13") (pinfunction "GND_13") (pintype "input"))
      (node (ref "U1") (pin "18") (pinfunction "GND_18") (pintype "input"))
      (node (ref "U1") (pin "20") (pinfunction "GND_20") (pintype "input"))
      (node (ref "U1") (pin "3") (pinfunction "GND_3") (pintype "input"))
      (node (ref "U1") (pin "37") (pinfunction "GND_37") (pintype "input"))
      (node (ref "U1") (pin "41") (pinfunction "GND_41") (pintype "input"))
      (node (ref "U1") (pin "44") (pinfunction "GND_44") (pintype "input"))
      (node (ref "U1") (pin "48") (pinfunction "GND_48") (pintype "input"))
      (node (ref "U1") (pin "9") (pinfunction "GND_9") (pintype "input"))
      (node (ref "U10") (pin "1") (pinfunction "E1_1") (pintype "input"))
      (node (ref "U10") (pin "2") (pinfunction "E2_2") (pintype "input"))
      (node (ref "U10") (pin "3") (pinfunction "E3_3") (pintype "input"))
      (node (ref "U10") (pin "4") (pinfunction "VSS_4") (pintype "input"))
      (node (ref "U10") (pin "7") (pinfunction "WC#_7") (pintype "input"))
      (node (ref "U11") (pin "5") (pinfunction "GND_5") (pintype "input"))
      (node (ref "U12") (pin "2") (pinfunction "2_2") (pintype "input"))
      (node (ref "U13") (pin "2") (pinfunction "GND_2") (pintype "input"))
      (node (ref "U5") (pin "1") (pinfunction "GND_1") (pintype "input"))
      (node (ref "U6") (pin "1") (pinfunction "GND_1") (pintype "input"))
      (node (ref "U7") (pin "23") (pinfunction "VSS_1_23") (pintype "input"))
      (node (ref "U7") (pin "35") (pinfunction "VSS_2_35") (pintype "input"))
      (node (ref "U7") (pin "47") (pinfunction "VSS_3_47") (pintype "input"))
      (node (ref "U7") (pin "8") (pinfunction "VSSA_8") (pintype "input"))
      (node (ref "U9") (pin "8") (pinfunction "E_8") (pintype "input"))
    )
    (net (code "12") (name "K11") (class "Default")
      (node (ref "CN1") (pin "1") (pinfunction "1_1") (pintype "input"))
      (node (ref "K1") (pin "3") (pinfunction "3_3") (pintype "input"))
    )
    (net (code "13") (name "K12") (class "Default")
      (node (ref "CN1") (pin "2") (pinfunction "2_2") (pintype "input"))
      (node (ref "K1") (pin "4") (pinfunction "4_4") (pintype "input"))
    )
    (net (code "14") (name "K21") (class "Default")
      (node (ref "CN2") (pin "1") (pinfunction "1_1") (pintype "input"))
      (node (ref "K2") (pin "3") (pinfunction "3_3") (pintype "input"))
    )
    (net (code "15") (name "K22") (class "Default")
      (node (ref "CN2") (pin "2") (pinfunction "2_2") (pintype "input"))
      (node (ref "K2") (pin "4") (pinfunction "4_4") (pintype "input"))
    )
    (net (code "16") (name "K31") (class "Default")
      (node (ref "CN3") (pin "1") (pinfunction "1_1") (pintype "input"))
      (node (ref "K3") (pin "3") (pinfunction "3_3") (pintype "input"))
    )
    (net (code "17") (name "K32") (class "Default")
      (node (ref "CN3") (pin "2") (pinfunction "2_2") (pintype "input"))
      (node (ref "K3") (pin "4") (pinfunction "4_4") (pintype "input"))
    )
    (net (code "18") (name "K41") (class "Default")
      (node (ref "CN4") (pin "1") (pinfunction "1_1") (pintype "input"))
      (node (ref "K4") (pin "3") (pinfunction "3_3") (pintype "input"))
    )
    (net (code "19") (name "K42") (class "Default")
      (node (ref "CN4") (pin "2") (pinfunction "2_2") (pintype "input"))
      (node (ref "K4") (pin "4") (pinfunction "4_4") (pintype "input"))
    )
    (net (code "20") (name "LINK#") (class "Default")
      (node (ref "J2") (pin "10") (pinfunction "10_10") (pintype "input"))
      (node (ref "J2") (pin "11") (pinfunction "11_11") (pintype "input"))
      (node (ref "U1") (pin "52") (pinfunction "LINK#_52") (pintype "input"))
    )
    (net (code "21") (name "M_C") (class "Default")
      (node (ref "R13") (pin "2") (pinfunction "2_2") (pintype "input"))
      (node (ref "U7") (pin "34") (pinfunction "PA13_34") (pintype "input"))
    )
    (net (code "22") (name "M_D") (class "Default")
      (node (ref "R12") (pin "2") (pinfunction "2_2") (pintype "input"))
      (node (ref "U7") (pin "37") (pinfunction "PA14_37") (pintype "input"))
    )
    (net (code "23") (name "M_DIR") (class "Default")
      (node (ref "R16") (pin "1") (pinfunction "1_1") (pintype "input"))
      (node (ref "U11") (pin "2") (pinfunction "#RE_2") (pintype "input"))
      (node (ref "U11") (pin "3") (pinfunction "DE_3") (pintype "input"))
      (node (ref "U7") (pin "33") (pinfunction "PA12_33") (pintype "input"))
    )
    (net (code "24") (name "M_IO_PA4") (class "Default")
      (node (ref "H2") (pin "1") (pinfunction "1_1") (pintype "input"))
      (node (ref "U7") (pin "14") (pinfunction "PA4_14") (pintype "input"))
    )
    (net (code "25") (name "M_IO_PA5") (class "Default")
      (node (ref "H2") (pin "3") (pinfunction "3_3") (pintype "input"))
      (node (ref "U7") (pin "15") (pinfunction "PA5_15") (pintype "input"))
    )
    (net (code "26") (name "M_IO_PA6") (class "Default")
      (node (ref "H2") (pin "5") (pinfunction "5_5") (pintype "input"))
      (node (ref "U7") (pin "16") (pinfunction "PA6_16") (pintype "input"))
    )
    (net (code "27") (name "M_IO_PA7") (class "Default")
      (node (ref "H2") (pin "7") (pinfunction "7_7") (pintype "input"))
      (node (ref "U7") (pin "17") (pinfunction "PA7_17") (pintype "input"))
    )
    (net (code "28") (name "M_IO_PB1") (class "Default")
      (node (ref "H2") (pin "2") (pinfunction "2_2") (pintype "input"))
      (node (ref "U7") (pin "19") (pinfunction "PB1_19") (pintype "input"))
    )
    (net (code "29") (name "M_IO_PB2") (class "Default")
      (node (ref "H2") (pin "4") (pinfunction "4_4") (pintype "input"))
      (node (ref "U7") (pin "20") (pinfunction "PB2_20") (pintype "input"))
    )
    (net (code "30") (name "M_IO_PB10") (class "Default")
      (node (ref "H2") (pin "6") (pinfunction "6_6") (pintype "input"))
      (node (ref "U7") (pin "21") (pinfunction "PB10_21") (pintype "input"))
    )
    (net (code "31") (name "M_IO_PB11") (class "Default")
      (node (ref "H2") (pin "8") (pinfunction "8_8") (pintype "input"))
      (node (ref "U7") (pin "22") (pinfunction "PB11_22") (pintype "input"))
    )
    (net (code "32") (name "M_K1") (class "Default")
      (node (ref "U7") (pin "10") (pinfunction "PA0-WKUP_10") (pintype "input"))
      (node (ref "U9") (pin "1") (pinfunction "1B_1") (pintype "input"))
      (node (ref "U9") (pin "2") (pinfunction "2B_2") (pintype "input"))
    )
    (net (code "33") (name "M_K2") (class "Default")
      (node (ref "U7") (pin "11") (pinfunction "PA1_11") (pintype "input"))
      (node (ref "U9") (pin "3") (pinfunction "3B_3") (pintype "input"))
      (node (ref "U9") (pin "4") (pinfunction "4B_4") (pintype "input"))
    )
    (net (code "34") (name "M_K3") (class "Default")
      (node (ref "U7") (pin "12") (pinfunction "PA2_12") (pintype "input"))
      (node (ref "U9") (pin "5") (pinfunction "5B_5") (pintype "input"))
      (node (ref "U9") (pin "6") (pinfunction "6B_6") (pintype "input"))
    )
    (net (code "35") (name "M_K4") (class "Default")
      (node (ref "U7") (pin "13") (pinfunction "PA3_13") (pintype "input"))
      (node (ref "U9") (pin "7") (pinfunction "7B_7") (pintype "input"))
    )
    (net (code "36") (name "M_KC1") (class "Default")
      (node (ref "K1") (pin "2") (pinfunction "2_2") (pintype "input"))
      (node (ref "U9") (pin "15") (pinfunction "2C_15") (pintype "input"))
      (node (ref "U9") (pin "16") (pinfunction "1C_16") (pintype "input"))
    )
    (net (code "37") (name "M_KC2") (class "Default")
      (node (ref "K2") (pin "2") (pinfunction "2_2") (pintype "input"))
      (node (ref "U9") (pin "13") (pinfunction "4C_13") (pintype "input"))
      (node (ref "U9") (pin "14") (pinfunction "3C_14") (pintype "input"))
    )
    (net (code "38") (name "M_KC3") (class "Default")
      (node (ref "K3") (pin "2") (pinfunction "2_2") (pintype "input"))
      (node (ref "U9") (pin "11") (pinfunction "6C_11") (pintype "input"))
      (node (ref "U9") (pin "12") (pinfunction "5C_12") (pintype "input"))
    )
    (net (code "39") (name "M_KC4") (class "Default")
      (node (ref "K4") (pin "2") (pinfunction "2_2") (pintype "input"))
      (node (ref "U9") (pin "10") (pinfunction "7C_10") (pintype "input"))
    )
    (net (code "40") (name "M_RST#") (class "Default")
      (node (ref "C28") (pin "1") (pinfunction "1_1") (pintype "input"))
      (node (ref "R11") (pin "1") (pinfunction "1_1") (pintype "input"))
      (node (ref "U7") (pin "7") (pinfunction "NRST_7") (pintype "input"))
    )
    (net (code "41") (name "M_RXD") (class "Default")
      (node (ref "R18") (pin "2") (pinfunction "2_2") (pintype "input"))
      (node (ref "U11") (pin "1") (pinfunction "RO_1") (pintype "input"))
      (node (ref "U7") (pin "31") (pinfunction "PA10_31") (pintype "input"))
    )
    (net (code "42") (name "M_SCL") (class "Default")
      (node (ref "R15") (pin "2") (pinfunction "2_2") (pintype "input"))
      (node (ref "U10") (pin "6") (pinfunction "SCL_6") (pintype "input"))
      (node (ref "U7") (pin "42") (pinfunction "PB6_42") (pintype "input"))
    )
    (net (code "43") (name "M_SDA") (class "Default")
      (node (ref "R14") (pin "1") (pinfunction "1_1") (pintype "input"))
      (node (ref "U10") (pin "5") (pinfunction "SDA_5") (pintype "input"))
      (node (ref "U7") (pin "43") (pinfunction "PB7_43") (pintype "input"))
    )
    (net (code "44") (name "M_TXD") (class "Default")
      (node (ref "R17") (pin "1") (pinfunction "1_1") (pintype "input"))
      (node (ref "U11") (pin "4") (pinfunction "DI_4") (pintype "input"))
      (node (ref "U7") (pin "30") (pinfunction "PA9_30") (pintype "input"))
    )
    (net (code "45") (name "M_X1") (class "Default")
      (node (ref "C33") (pin "2") (pinfunction "2_2") (pintype "input"))
      (node (ref "U7") (pin "5") (pinfunction "PD0-OSCIN_5") (pintype "input"))
      (node (ref "U8") (pin "2") (pinfunction "2_2") (pintype "input"))
    )
    (net (code "46") (name "M_X2") (class "Default")
      (node (ref "C34") (pin "2") (pinfunction "2_2") (pintype "input"))
      (node (ref "U7") (pin "6") (pinfunction "PD1-OSCOUT_6") (pintype "input"))
      (node (ref "U8") (pin "1") (pinfunction "1_1") (pintype "input"))
    )
    (net (code "47") (name "Net-(H1-Pad1)") (class "Default")
      (node (ref "H1") (pin "1") (pinfunction "1_1") (pintype "input"))
      (node (ref "R12") (pin "1") (pinfunction "1_1") (pintype "input"))
    )
    (net (code "48") (name "Net-(H1-Pad4)") (class "Default")
      (node (ref "H1") (pin "4") (pinfunction "4_4") (pintype "input"))
      (node (ref "R13") (pin "1") (pinfunction "1_1") (pintype "input"))
    )
    (net (code "49") (name "Net-(J2-CHS_GND)") (class "Default")
      (node (ref "J2") (pin "8") (pinfunction "CHS_GND_8") (pintype "input"))
      (node (ref "R2") (pin "1") (pinfunction "1_1") (pintype "input"))
    )
    (net (code "50") (name "Net-(J2-Pad9)") (class "Default")
      (node (ref "J2") (pin "9") (pinfunction "9_9") (pintype "input"))
      (node (ref "R6") (pin "1") (pinfunction "1_1") (pintype "input"))
    )
    (net (code "51") (name "Net-(J2-Pad12)") (class "Default")
      (node (ref "J2") (pin "12") (pinfunction "12_12") (pintype "input"))
      (node (ref "R7") (pin "1") (pinfunction "1_1") (pintype "input"))
    )
    (net (code "52") (name "Net-(U1-RSETE)") (class "Default")
      (node (ref "R4") (pin "1") (pinfunction "1_1") (pintype "input"))
      (node (ref "U1") (pin "1") (pinfunction "RSETE_1") (pintype "input"))
    )
    (net (code "53") (name "Net-(U1-TXD)") (class "Default")
      (node (ref "R1") (pin "1") (pinfunction "1_1") (pintype "input"))
      (node (ref "U1") (pin "58") (pinfunction "TXD_58") (pintype "input"))
    )
    (net (code "54") (name "Net-(U11-A)") (class "Default")
      (node (ref "CN5") (pin "1") (pinfunction "1_1") (pintype "input"))
      (node (ref "R19") (pin "1") (pinfunction "1_1") (pintype "input"))
      (node (ref "R21") (pin "2") (pinfunction "2_2") (pintype "input"))
      (node (ref "U11") (pin "6") (pinfunction "A_6") (pintype "input"))
    )
    (net (code "55") (name "Net-(U11-B)") (class "Default")
      (node (ref "CN5") (pin "2") (pinfunction "2_2") (pintype "input"))
      (node (ref "R20") (pin "2") (pinfunction "2_2") (pintype "input"))
      (node (ref "R21") (pin "1") (pinfunction "1_1") (pintype "input"))
      (node (ref "U11") (pin "7") (pinfunction "B_7") (pintype "input"))
    )
    (net (code "56") (name "PGND") (class "Default")
      (node (ref "J2") (pin "SH1") (pinfunction "SH1_SH1") (pintype "input"))
      (node (ref "J2") (pin "SH2") (pinfunction "SH2_SH2") (pintype "input"))
      (node (ref "TP1") (pin "1") (pinfunction "1_1") (pintype "input"))
    )
    (net (code "57") (name "RXN") (class "Default")
      (node (ref "J2") (pin "6") (pinfunction "RD-_6") (pintype "input"))
      (node (ref "R3") (pin "1") (pinfunction "1_1") (pintype "input"))
      (node (ref "U1") (pin "5") (pinfunction "RXN_5") (pintype "input"))
    )
    (net (code "58") (name "RXP") (class "Default")
      (node (ref "J2") (pin "3") (pinfunction "RD+_3") (pintype "input"))
      (node (ref "R5") (pin "1") (pinfunction "1_1") (pintype "input"))
      (node (ref "U1") (pin "4") (pinfunction "RXP_4") (pintype "input"))
    )
    (net (code "59") (name "SEN_OUT") (class "Default")
      (node (ref "C39") (pin "1") (pinfunction "1_1") (pintype "input"))
      (node (ref "R22") (pin "1") (pinfunction "1_1") (pintype "input"))
      (node (ref "U12") (pin "4") (pinfunction "4_4") (pintype "input"))
      (node (ref "U7") (pin "18") (pinfunction "PB0_18") (pintype "input"))
    )
    (net (code "60") (name "S_CTRL") (class "Default")
      (node (ref "R23") (pin "2") (pinfunction "2_2") (pintype "input"))
      (node (ref "U13") (pin "4") (pinfunction "EN#_4") (pintype "input"))
      (node (ref "U7") (pin "38") (pinfunction "PA15_38") (pintype "input"))
    )
    (net (code "61") (name "TXN") (class "Default")
      (node (ref "J2") (pin "2") (pinfunction "TD-_2") (pintype "input"))
      (node (ref "R8") (pin "1") (pinfunction "1_1") (pintype "input"))
      (node (ref "U1") (pin "8") (pinfunction "TXN_8") (pintype "input"))
    )
    (net (code "62") (name "TXP") (class "Default")
      (node (ref "J2") (pin "1") (pinfunction "TD+_1") (pintype "input"))
      (node (ref "R9") (pin "1") (pinfunction "1_1") (pintype "input"))
      (node (ref "U1") (pin "7") (pinfunction "TXP_7") (pintype "input"))
    )
    (net (code "63") (name "V_HU") (class "Default")
      (node (ref "C40") (pin "2") (pinfunction "2_2") (pintype "input"))
      (node (ref "C42") (pin "2") (pinfunction "2_2") (pintype "input"))
      (node (ref "U12") (pin "1") (pinfunction "1_1") (pintype "input"))
      (node (ref "U13") (pin "1") (pinfunction "VOUT_1") (pintype "input"))
    )
    (net (code "64") (name "XI") (class "Default")
      (node (ref "C16") (pin "2") (pinfunction "2_2") (pintype "input"))
      (node (ref "U1") (pin "10") (pinfunction "XI_10") (pintype "input"))
      (node (ref "X1") (pin "2") (pinfunction "OSC2_2") (pintype "input"))
    )
    (net (code "65") (name "XO") (class "Default")
      (node (ref "C17") (pin "2") (pinfunction "2_2") (pintype "input"))
      (node (ref "U1") (pin "11") (pinfunction "XO_11") (pintype "input"))
      (node (ref "X1") (pin "1") (pinfunction "OSC1_1") (pintype "input"))
    )
    (net (code "66") (name "unconnected-(J2-NC-Pad7)") (class "Default")
      (node (ref "J2") (pin "7") (pinfunction "NC_7") (pintype "input+no_connect"))
    )
    (net (code "67") (name "unconnected-(OLED1-GND-Pad1)") (class "Default")
      (node (ref "OLED1") (pin "1") (pinfunction "GND_1") (pintype "input"))
    )
    (net (code "68") (name "unconnected-(OLED1-SCL-Pad3)") (class "Default")
      (node (ref "OLED1") (pin "3") (pinfunction "SCL_3") (pintype "input"))
    )
    (net (code "69") (name "unconnected-(OLED1-SDA-Pad4)") (class "Default")
      (node (ref "OLED1") (pin "4") (pinfunction "SDA_4") (pintype "input"))
    )
    (net (code "70") (name "unconnected-(OLED1-VCC-Pad2)") (class "Default")
      (node (ref "OLED1") (pin "2") (pinfunction "VCC_2") (pintype "input"))
    )
    (net (code "71") (name "unconnected-(U1-GPIO0-Pad22)") (class "Default")
      (node (ref "U1") (pin "22") (pinfunction "GPIO0_22") (pintype "input+no_connect"))
    )
    (net (code "72") (name "unconnected-(U1-GPIO1-Pad23)") (class "Default")
      (node (ref "U1") (pin "23") (pinfunction "GPIO1_23") (pintype "input+no_connect"))
    )
    (net (code "73") (name "unconnected-(U1-GPIO2-Pad24)") (class "Default")
      (node (ref "U1") (pin "24") (pinfunction "GPIO2_24") (pintype "input+no_connect"))
    )
    (net (code "74") (name "unconnected-(U1-GPIO4-Pad32)") (class "Default")
      (node (ref "U1") (pin "32") (pinfunction "GPIO4_32") (pintype "input+no_connect"))
    )
    (net (code "75") (name "unconnected-(U1-GPIO5-Pad33)") (class "Default")
      (node (ref "U1") (pin "33") (pinfunction "GPIO5_33") (pintype "input+no_connect"))
    )
    (net (code "76") (name "unconnected-(U1-GPIO6-Pad34)") (class "Default")
      (node (ref "U1") (pin "34") (pinfunction "GPIO6_34") (pintype "input+no_connect"))
    )
    (net (code "77") (name "unconnected-(U1-GPIO7-Pad35)") (class "Default")
      (node (ref "U1") (pin "35") (pinfunction "GPIO7_35") (pintype "input+no_connect"))
    )
    (net (code "78") (name "unconnected-(U1-NC-Pad14)") (class "Default")
      (node (ref "U1") (pin "14") (pinfunction "NC_14") (pintype "input+no_connect"))
    )
    (net (code "79") (name "unconnected-(U1-NC-Pad15)") (class "Default")
      (node (ref "U1") (pin "15") (pinfunction "NC_15") (pintype "input+no_connect"))
    )
    (net (code "80") (name "unconnected-(U1-NC-Pad16)") (class "Default")
      (node (ref "U1") (pin "16") (pinfunction "NC_16") (pintype "input+no_connect"))
    )
    (net (code "81") (name "unconnected-(U1-NC-Pad30)") (class "Default")
      (node (ref "U1") (pin "30") (pinfunction "NC_30") (pintype "input+no_connect"))
    )
    (net (code "82") (name "unconnected-(U1-NC-Pad31)") (class "Default")
      (node (ref "U1") (pin "31") (pinfunction "NC_31") (pintype "input+no_connect"))
    )
    (net (code "83") (name "unconnected-(U1-NC-Pad38)") (class "Default")
      (node (ref "U1") (pin "38") (pinfunction "NC_38") (pintype "input+no_connect"))
    )
    (net (code "84") (name "unconnected-(U1-NC-Pad39)") (class "Default")
      (node (ref "U1") (pin "39") (pinfunction "NC_39") (pintype "input+no_connect"))
    )
    (net (code "85") (name "unconnected-(U1-NC-Pad46)") (class "Default")
      (node (ref "U1") (pin "46") (pinfunction "NC_46") (pintype "input+no_connect"))
    )
    (net (code "86") (name "unconnected-(U1-NC-Pad47)") (class "Default")
      (node (ref "U1") (pin "47") (pinfunction "NC_47") (pintype "input+no_connect"))
    )
    (net (code "87") (name "unconnected-(U1-NC-Pad50)") (class "Default")
      (node (ref "U1") (pin "50") (pinfunction "NC_50") (pintype "input+no_connect"))
    )
    (net (code "88") (name "unconnected-(U1-NC-Pad51)") (class "Default")
      (node (ref "U1") (pin "51") (pinfunction "NC_51") (pintype "input+no_connect"))
    )
    (net (code "89") (name "unconnected-(U1-NC-Pad53)") (class "Default")
      (node (ref "U1") (pin "53") (pinfunction "NC_53") (pintype "input+no_connect"))
    )
    (net (code "90") (name "unconnected-(U1-NC-Pad55)") (class "Default")
      (node (ref "U1") (pin "55") (pinfunction "NC_55") (pintype "input+no_connect"))
    )
    (net (code "91") (name "unconnected-(U1-NC-Pad56)") (class "Default")
      (node (ref "U1") (pin "56") (pinfunction "NC_56") (pintype "input+no_connect"))
    )
    (net (code "92") (name "unconnected-(U1-RDY#GPIO3-Pad25)") (class "Default")
      (node (ref "U1") (pin "25") (pinfunction "RDY#GPIO3_25") (pintype "input+no_connect"))
    )
    (net (code "93") (name "unconnected-(U1-RST-Pad26)") (class "Default")
      (node (ref "U1") (pin "26") (pinfunction "RST_26") (pintype "input+no_connect"))
    )
    (net (code "94") (name "unconnected-(U1-RXD-Pad57)") (class "Default")
      (node (ref "U1") (pin "57") (pinfunction "RXD_57") (pintype "input+no_connect"))
    )
    (net (code "95") (name "unconnected-(U1-SEL-Pad27)") (class "Default")
      (node (ref "U1") (pin "27") (pinfunction "SEL_27") (pintype "input+no_connect"))
    )
    (net (code "96") (name "unconnected-(U7-PB3-Pad39)") (class "Default")
      (node (ref "U7") (pin "39") (pinfunction "PB3_39") (pintype "input+no_connect"))
    )
    (net (code "97") (name "unconnected-(U7-PB4-Pad40)") (class "Default")
      (node (ref "U7") (pin "40") (pinfunction "PB4_40") (pintype "input+no_connect"))
    )
    (net (code "98") (name "unconnected-(U7-PB5-Pad41)") (class "Default")
      (node (ref "U7") (pin "41") (pinfunction "PB5_41") (pintype "input+no_connect"))
    )
    (net (code "99") (name "unconnected-(U7-PB8-Pad45)") (class "Default")
      (node (ref "U7") (pin "45") (pinfunction "PB8_45") (pintype "input+no_connect"))
    )
    (net (code "100") (name "unconnected-(U7-PB9-Pad46)") (class "Default")
      (node (ref "U7") (pin "46") (pinfunction "PB9_46") (pintype "input+no_connect"))
    )
    (net (code "101") (name "unconnected-(U7-PC13-TAMPER-RTC-Pad2)") (class "Default")
      (node (ref "U7") (pin "2") (pinfunction "PC13-TAMPER-RTC_2") (pintype "input+no_connect"))
    )
    (net (code "102") (name "unconnected-(U7-PC14-OSC32IN-Pad3)") (class "Default")
      (node (ref "U7") (pin "3") (pinfunction "PC14-OSC32IN_3") (pintype "input+no_connect"))
    )
    (net (code "103") (name "unconnected-(U7-PC15-OSC32OUT-Pad4)") (class "Default")
      (node (ref "U7") (pin "4") (pinfunction "PC15-OSC32OUT_4") (pintype "input+no_connect"))
    )
    (net (code "104") (name "unconnected-(U13-FAULT-Pad5)") (class "Default")
      (node (ref "U13") (pin "5") (pinfunction "FAULT_5") (pintype "input+no_connect"))
    )
  )
)
